# SD_Card.net
KiCad netlist of a schematic drawn in Altium Designer
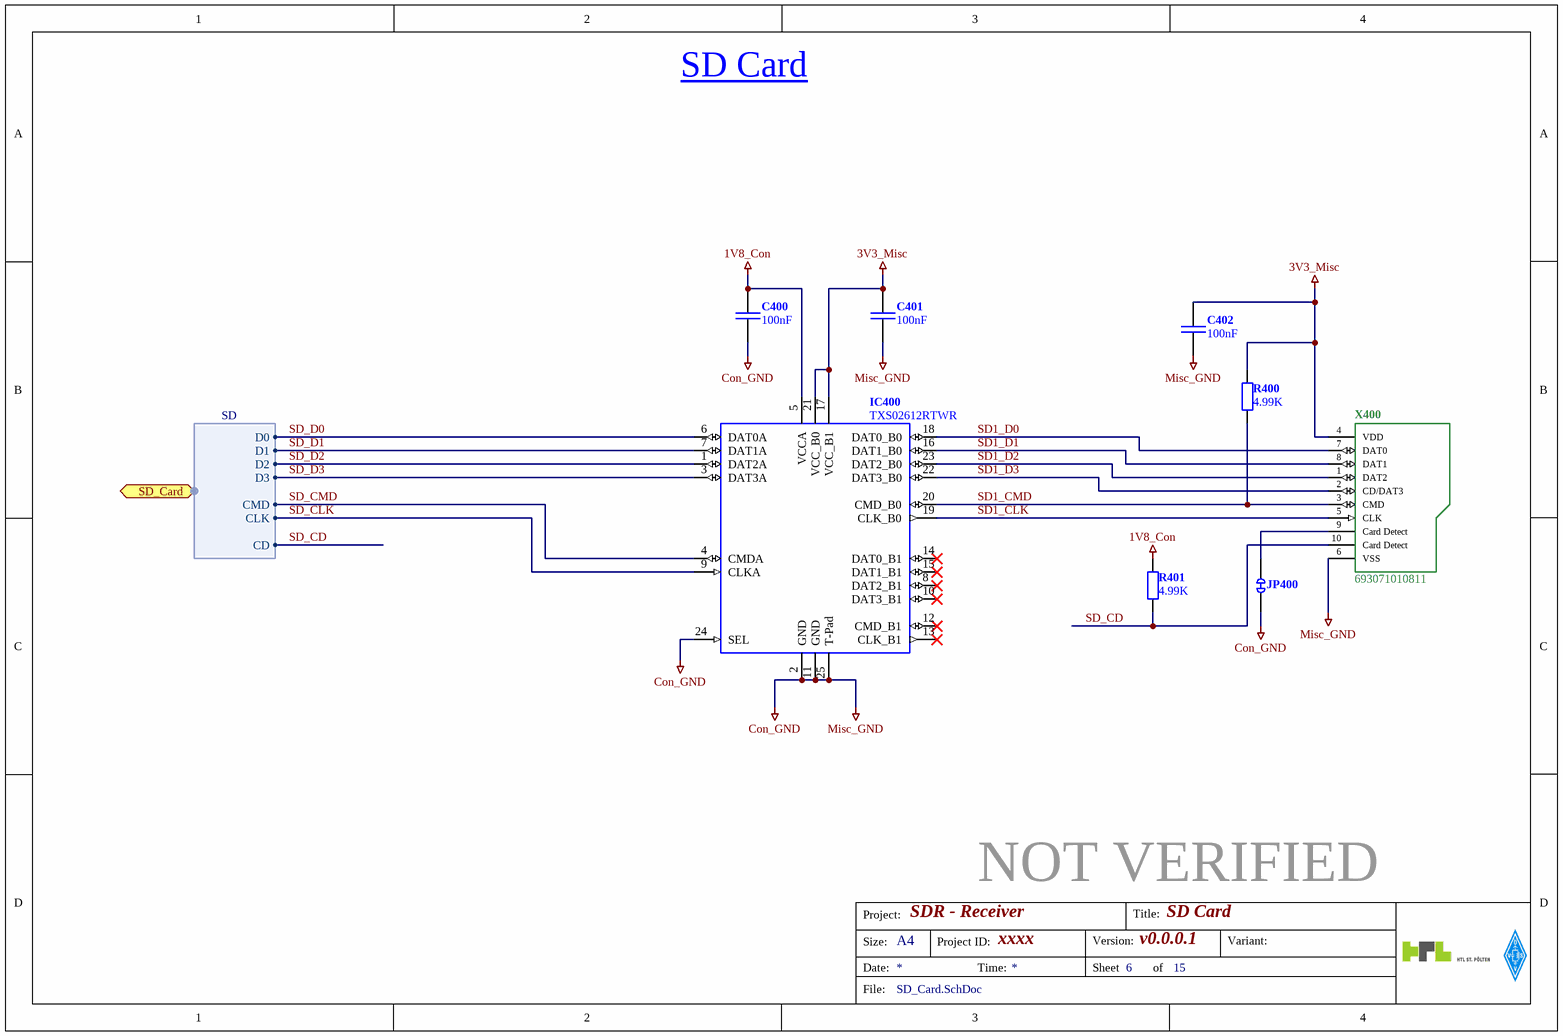
[diagram p0: SD_Card.SchDoc]

(export (version "E")
  (design (tool "Eeschema 10.0.6"))
  (components
    (comp (ref "C400")
      (value "100nF")
      (footprint "PrometheusLib:C_0603_N [CAPC1608N IPC]")
      (libsource (lib "PrometheusLib") (part "C_GENERIC"))
    )
    (comp (ref "C401")
      (value "100nF")
      (footprint "PrometheusLib:C_0603_N [CAPC1608N IPC]")
      (libsource (lib "PrometheusLib") (part "C_GENERIC"))
    )
    (comp (ref "C402")
      (value "100nF")
      (footprint "PrometheusLib:C_0603_N [CAPC1608N IPC]")
      (libsource (lib "PrometheusLib") (part "C_GENERIC"))
    )
    (comp (ref "IC400")
      (value "TXS02612RTWR")
      (footprint "QFN50P400X400X80_HS-25N IPC")
      (libsource (lib "PrometheusLib") (part "IC_TXS02612"))
    )
    (comp (ref "JP400")
      (value "JP_Connected")
      (footprint "JP_Connected")
      (libsource (lib "PrometheusLib") (part "JP_Connected"))
    )
    (comp (ref "R400")
      (value "4.99K")
      (footprint "PrometheusLib:R_0603_N [RESC1608N IPC]")
      (libsource (lib "PrometheusLib") (part "R_GENERIC_DIN"))
    )
    (comp (ref "R401")
      (value "4.99K")
      (footprint "PrometheusLib:R_0603_N [RESC1608N IPC]")
      (libsource (lib "PrometheusLib") (part "R_GENERIC_DIN"))
    )
    (comp (ref "X400")
      (value "693071010811")
      (footprint "X_693071010811")
      (description "WR-CRD Micro SD Card Connector, Push & Push, with card detection")
      (libsource (lib "PrometheusLib") (part "X_693071010811"))
    )
  )
  (nets
    (net (code "2") (name "/SD1_CLK") (class "Default")
      (node (ref "IC400") (pin "19") (pinfunction "CLK_B0_19") (pintype "output"))
      (node (ref "X400") (pin "5") (pinfunction "CLK_5") (pintype "input"))
    )
    (net (code "3") (name "/SD1_CMD") (class "Default")
      (node (ref "IC400") (pin "20") (pinfunction "CMD_B0_20") (pintype "bidirectional"))
      (node (ref "R400") (pin "1") (pinfunction "1_1") (pintype "passive"))
      (node (ref "X400") (pin "3") (pinfunction "CMD_3") (pintype "bidirectional"))
    )
    (net (code "4") (name "/SD1_D0") (class "Default")
      (node (ref "IC400") (pin "18") (pinfunction "DAT0_B0_18") (pintype "bidirectional"))
      (node (ref "X400") (pin "7") (pinfunction "DAT0_7") (pintype "bidirectional"))
    )
    (net (code "5") (name "/SD1_D1") (class "Default")
      (node (ref "IC400") (pin "16") (pinfunction "DAT1_B0_16") (pintype "bidirectional"))
      (node (ref "X400") (pin "8") (pinfunction "DAT1_8") (pintype "bidirectional"))
    )
    (net (code "6") (name "/SD1_D2") (class "Default")
      (node (ref "IC400") (pin "23") (pinfunction "DAT2_B0_23") (pintype "bidirectional"))
      (node (ref "X400") (pin "1") (pinfunction "DAT2_1") (pintype "bidirectional"))
    )
    (net (code "7") (name "/SD1_D3") (class "Default")
      (node (ref "IC400") (pin "22") (pinfunction "DAT3_B0_22") (pintype "bidirectional"))
      (node (ref "X400") (pin "2") (pinfunction "CD/DAT3_2") (pintype "bidirectional"))
    )
    (net (code "8") (name "/SD_CD") (class "Default")
      (node (ref "R401") (pin "1") (pinfunction "1_1") (pintype "passive"))
      (node (ref "X400") (pin "10") (pinfunction "Card_Detect_10") (pintype "passive"))
    )
    (net (code "9") (name "/SD_CLK") (class "Default")
      (node (ref "IC400") (pin "9") (pinfunction "CLKA_9") (pintype "input"))
    )
    (net (code "10") (name "/SD_CMD") (class "Default")
      (node (ref "IC400") (pin "4") (pinfunction "CMDA_4") (pintype "bidirectional"))
    )
    (net (code "11") (name "/SD_D0") (class "Default")
      (node (ref "IC400") (pin "6") (pinfunction "DAT0A_6") (pintype "bidirectional"))
    )
    (net (code "12") (name "/SD_D1") (class "Default")
      (node (ref "IC400") (pin "7") (pinfunction "DAT1A_7") (pintype "bidirectional"))
    )
    (net (code "13") (name "/SD_D2") (class "Default")
      (node (ref "IC400") (pin "1") (pinfunction "DAT2A_1") (pintype "bidirectional"))
    )
    (net (code "14") (name "/SD_D3") (class "Default")
      (node (ref "IC400") (pin "3") (pinfunction "DAT3A_3") (pintype "bidirectional"))
    )
    (net (code "16") (name "1V8_Con") (class "Default")
      (node (ref "C400") (pin "1") (pintype "passive"))
      (node (ref "IC400") (pin "5") (pinfunction "VCCA_5") (pintype "passive"))
      (node (ref "R401") (pin "2") (pinfunction "2_2") (pintype "passive"))
    )
    (net (code "17") (name "3V3_Misc") (class "Default")
      (node (ref "C401") (pin "1") (pintype "passive"))
      (node (ref "C402") (pin "1") (pintype "passive"))
      (node (ref "IC400") (pin "17") (pinfunction "VCC_B1_17") (pintype "passive"))
      (node (ref "IC400") (pin "21") (pinfunction "VCC_B0_21") (pintype "passive"))
      (node (ref "R400") (pin "2") (pinfunction "2_2") (pintype "passive"))
      (node (ref "X400") (pin "4") (pinfunction "VDD_4") (pintype "passive"))
    )
    (net (code "18") (name "Con_GND") (class "Default")
      (node (ref "C400") (pin "2") (pintype "passive"))
      (node (ref "C401") (pin "2") (pintype "passive"))
      (node (ref "C402") (pin "2") (pintype "passive"))
      (node (ref "IC400") (pin "11") (pinfunction "GND_11") (pintype "passive"))
      (node (ref "IC400") (pin "2") (pinfunction "GND_2") (pintype "passive"))
      (node (ref "IC400") (pin "24") (pinfunction "SEL_24") (pintype "input"))
      (node (ref "IC400") (pin "25") (pinfunction "T-Pad_25") (pintype "passive"))
      (node (ref "JP400") (pin "2") (pinfunction "-_2") (pintype "passive"))
      (node (ref "X400") (pin "6") (pinfunction "VSS_6") (pintype "passive"))
    )
    (net (code "19") (name "Net-(JP400-+)") (class "Default")
      (node (ref "JP400") (pin "1") (pinfunction "+_1") (pintype "passive"))
      (node (ref "X400") (pin "9") (pinfunction "Card_Detect_9") (pintype "passive"))
    )
    (net (code "20") (name "unconnected-(IC400-CLK_B1-Pad13)") (class "Default")
      (node (ref "IC400") (pin "13") (pinfunction "CLK_B1_13") (pintype "output+no_connect"))
    )
    (net (code "21") (name "unconnected-(IC400-CMD_B1-Pad12)") (class "Default")
      (node (ref "IC400") (pin "12") (pinfunction "CMD_B1_12") (pintype "bidirectional+no_connect"))
    )
    (net (code "22") (name "unconnected-(IC400-DAT0_B1-Pad14)") (class "Default")
      (node (ref "IC400") (pin "14") (pinfunction "DAT0_B1_14") (pintype "bidirectional+no_connect"))
    )
    (net (code "23") (name "unconnected-(IC400-DAT1_B1-Pad15)") (class "Default")
      (node (ref "IC400") (pin "15") (pinfunction "DAT1_B1_15") (pintype "bidirectional+no_connect"))
    )
    (net (code "24") (name "unconnected-(IC400-DAT2_B1-Pad8)") (class "Default")
      (node (ref "IC400") (pin "8") (pinfunction "DAT2_B1_8") (pintype "bidirectional+no_connect"))
    )
    (net (code "25") (name "unconnected-(IC400-DAT3_B1-Pad10)") (class "Default")
      (node (ref "IC400") (pin "10") (pinfunction "DAT3_B1_10") (pintype "bidirectional+no_connect"))
    )
  )
)
